# Display.net
KiCad netlist of a schematic drawn in Altium Designer
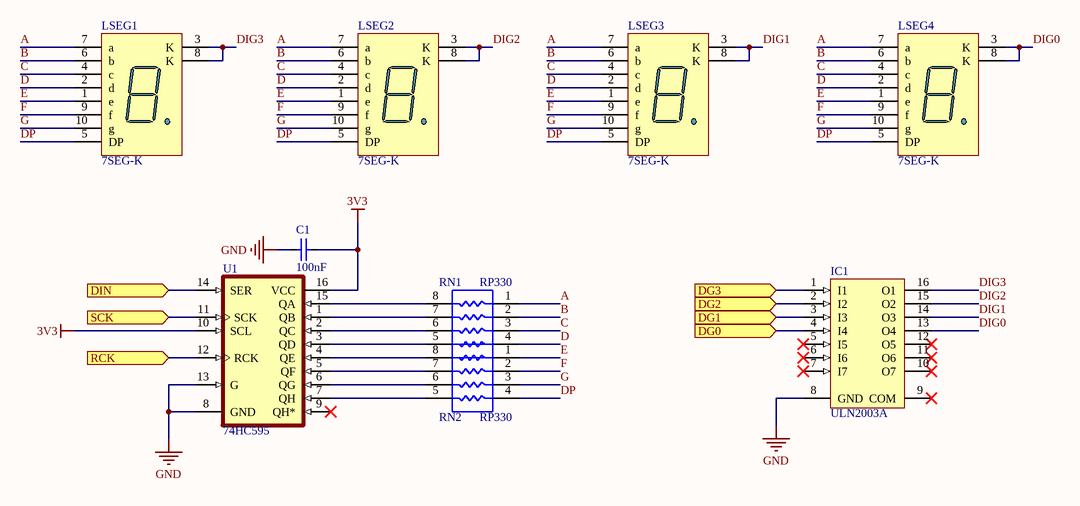
[diagram p0: Display.SchDoc]

(export (version "E")
  (design (tool "Eeschema 10.0.6"))
  (components
    (comp (ref "C1")
      (value "100nF")
      (footprint "CAP_0805")
      (description "Capacitor")
      (fields (field (name "PUBLISHER") "Altium Limited"))
      (libsource (lib "My Library") (part "CapSMD"))
    )
    (comp (ref "IC1")
      (value "ULN2003A")
      (footprint "SOIC16")
      (description "High-Voltage, High-Current Darlington Array")
      (fields (field (name "PUBLISHER") "Altium Limited"))
      (libsource (lib "My Library") (part "ULN2003A"))
    )
    (comp (ref "LSEG1")
      (value "7SEG-K")
      (footprint "LED7SEG")
      (description "14.2 mm General Purpose Blue 7-Segment Display: CC, RH DP, Gray Surface")
      (fields (field (name "PUBLISHER") "Altium Limited"))
      (libsource (lib "My Library") (part "LED7SEG-K"))
    )
    (comp (ref "LSEG2")
      (value "7SEG-K")
      (footprint "LED7SEG")
      (description "14.2 mm General Purpose Blue 7-Segment Display: CC, RH DP, Gray Surface")
      (fields (field (name "PUBLISHER") "Altium Limited"))
      (libsource (lib "My Library") (part "LED7SEG-K"))
    )
    (comp (ref "LSEG3")
      (value "7SEG-K")
      (footprint "LED7SEG")
      (description "14.2 mm General Purpose Blue 7-Segment Display: CC, RH DP, Gray Surface")
      (fields (field (name "PUBLISHER") "Altium Limited"))
      (libsource (lib "My Library") (part "LED7SEG-K"))
    )
    (comp (ref "LSEG4")
      (value "7SEG-K")
      (footprint "LED7SEG")
      (description "14.2 mm General Purpose Blue 7-Segment Display: CC, RH DP, Gray Surface")
      (fields (field (name "PUBLISHER") "Altium Limited"))
      (libsource (lib "My Library") (part "LED7SEG-K"))
    )
    (comp (ref "RN1") (value "RP330") (footprint "RN4-0805") (libsource (lib "My Library") (part "RN4-Dual")))
    (comp (ref "RN2") (value "RP330") (footprint "RN4-0805") (libsource (lib "My Library") (part "RN4-Dual")))
    (comp (ref "U1")
      (value "74HC595")
      (footprint "SOIC16")
      (description "8-bit Serial-Input/Serial or Parallel Output Shift Register with Latched 3-state Outputs")
      (libsource (lib "My Library") (part "74HC595"))
    )
  )
  (nets
    (net (code "1") (name "/A") (class "Default")
      (node (ref "LSEG1") (pin "7") (pinfunction "a_7") (pintype "passive"))
      (node (ref "LSEG2") (pin "7") (pinfunction "a_7") (pintype "passive"))
      (node (ref "LSEG3") (pin "7") (pinfunction "a_7") (pintype "passive"))
      (node (ref "LSEG4") (pin "7") (pinfunction "a_7") (pintype "passive"))
      (node (ref "RN1") (pin "1") (pinfunction "1_1") (pintype "passive"))
    )
    (net (code "2") (name "/B") (class "Default")
      (node (ref "LSEG1") (pin "6") (pinfunction "b_6") (pintype "passive"))
      (node (ref "LSEG2") (pin "6") (pinfunction "b_6") (pintype "passive"))
      (node (ref "LSEG3") (pin "6") (pinfunction "b_6") (pintype "passive"))
      (node (ref "LSEG4") (pin "6") (pinfunction "b_6") (pintype "passive"))
      (node (ref "RN1") (pin "2") (pinfunction "2_2") (pintype "passive"))
    )
    (net (code "3") (name "/C") (class "Default")
      (node (ref "LSEG1") (pin "4") (pinfunction "c_4") (pintype "passive"))
      (node (ref "LSEG2") (pin "4") (pinfunction "c_4") (pintype "passive"))
      (node (ref "LSEG3") (pin "4") (pinfunction "c_4") (pintype "passive"))
      (node (ref "LSEG4") (pin "4") (pinfunction "c_4") (pintype "passive"))
      (node (ref "RN1") (pin "3") (pinfunction "3_3") (pintype "passive"))
    )
    (net (code "4") (name "/D") (class "Default")
      (node (ref "LSEG1") (pin "2") (pinfunction "d_2") (pintype "passive"))
      (node (ref "LSEG2") (pin "2") (pinfunction "d_2") (pintype "passive"))
      (node (ref "LSEG3") (pin "2") (pinfunction "d_2") (pintype "passive"))
      (node (ref "LSEG4") (pin "2") (pinfunction "d_2") (pintype "passive"))
      (node (ref "RN1") (pin "4") (pinfunction "4_4") (pintype "passive"))
    )
    (net (code "5") (name "/DG0") (class "Default")
      (node (ref "IC1") (pin "4") (pinfunction "I4_4") (pintype "input"))
    )
    (net (code "6") (name "/DG1") (class "Default")
      (node (ref "IC1") (pin "3") (pinfunction "I3_3") (pintype "input"))
    )
    (net (code "7") (name "/DG2") (class "Default")
      (node (ref "IC1") (pin "2") (pinfunction "I2_2") (pintype "input"))
    )
    (net (code "8") (name "/DG3") (class "Default")
      (node (ref "IC1") (pin "1") (pinfunction "I1_1") (pintype "input"))
    )
    (net (code "9") (name "/DIG0") (class "Default")
      (node (ref "IC1") (pin "13") (pinfunction "O4_13") (pintype "open_collector"))
      (node (ref "LSEG4") (pin "3") (pinfunction "K_3") (pintype "passive"))
      (node (ref "LSEG4") (pin "8") (pinfunction "K_8") (pintype "passive"))
    )
    (net (code "10") (name "/DIG1") (class "Default")
      (node (ref "IC1") (pin "14") (pinfunction "O3_14") (pintype "open_collector"))
      (node (ref "LSEG3") (pin "3") (pinfunction "K_3") (pintype "passive"))
      (node (ref "LSEG3") (pin "8") (pinfunction "K_8") (pintype "passive"))
    )
    (net (code "11") (name "/DIG2") (class "Default")
      (node (ref "IC1") (pin "15") (pinfunction "O2_15") (pintype "open_collector"))
      (node (ref "LSEG2") (pin "3") (pinfunction "K_3") (pintype "passive"))
      (node (ref "LSEG2") (pin "8") (pinfunction "K_8") (pintype "passive"))
    )
    (net (code "12") (name "/DIG3") (class "Default")
      (node (ref "IC1") (pin "16") (pinfunction "O1_16") (pintype "open_collector"))
      (node (ref "LSEG1") (pin "3") (pinfunction "K_3") (pintype "passive"))
      (node (ref "LSEG1") (pin "8") (pinfunction "K_8") (pintype "passive"))
    )
    (net (code "13") (name "/DIN") (class "Default")
      (node (ref "U1") (pin "14") (pinfunction "SER_14") (pintype "input"))
    )
    (net (code "14") (name "/DP") (class "Default")
      (node (ref "LSEG1") (pin "5") (pinfunction "DP_5") (pintype "passive"))
      (node (ref "LSEG2") (pin "5") (pinfunction "DP_5") (pintype "passive"))
      (node (ref "LSEG3") (pin "5") (pinfunction "DP_5") (pintype "passive"))
      (node (ref "LSEG4") (pin "5") (pinfunction "DP_5") (pintype "passive"))
      (node (ref "RN2") (pin "4") (pinfunction "4_4") (pintype "passive"))
    )
    (net (code "15") (name "/E") (class "Default")
      (node (ref "LSEG1") (pin "1") (pinfunction "e_1") (pintype "passive"))
      (node (ref "LSEG2") (pin "1") (pinfunction "e_1") (pintype "passive"))
      (node (ref "LSEG3") (pin "1") (pinfunction "e_1") (pintype "passive"))
      (node (ref "LSEG4") (pin "1") (pinfunction "e_1") (pintype "passive"))
      (node (ref "RN2") (pin "1") (pinfunction "1_1") (pintype "passive"))
    )
    (net (code "16") (name "/F") (class "Default")
      (node (ref "LSEG1") (pin "9") (pinfunction "f_9") (pintype "passive"))
      (node (ref "LSEG2") (pin "9") (pinfunction "f_9") (pintype "passive"))
      (node (ref "LSEG3") (pin "9") (pinfunction "f_9") (pintype "passive"))
      (node (ref "LSEG4") (pin "9") (pinfunction "f_9") (pintype "passive"))
      (node (ref "RN2") (pin "2") (pinfunction "2_2") (pintype "passive"))
    )
    (net (code "17") (name "/G") (class "Default")
      (node (ref "LSEG1") (pin "10") (pinfunction "g_10") (pintype "passive"))
      (node (ref "LSEG2") (pin "10") (pinfunction "g_10") (pintype "passive"))
      (node (ref "LSEG3") (pin "10") (pinfunction "g_10") (pintype "passive"))
      (node (ref "LSEG4") (pin "10") (pinfunction "g_10") (pintype "passive"))
      (node (ref "RN2") (pin "3") (pinfunction "3_3") (pintype "passive"))
    )
    (net (code "18") (name "/RCK") (class "Default")
      (node (ref "U1") (pin "12") (pinfunction "RCK_12") (pintype "input"))
    )
    (net (code "19") (name "/SCK") (class "Default")
      (node (ref "U1") (pin "11") (pinfunction "SCK_11") (pintype "input"))
    )
    (net (code "20") (name "3V3") (class "Default")
      (node (ref "C1") (pin "1") (pinfunction "1_1") (pintype "passive"))
      (node (ref "U1") (pin "10") (pinfunction "SCL_10") (pintype "input"))
      (node (ref "U1") (pin "16") (pinfunction "VCC_16") (pintype "power_in"))
    )
    (net (code "21") (name "GND") (class "Default")
      (node (ref "C1") (pin "2") (pinfunction "2_2") (pintype "passive"))
      (node (ref "IC1") (pin "8") (pinfunction "GND_8") (pintype "power_in"))
      (node (ref "U1") (pin "13") (pinfunction "G_13") (pintype "input"))
      (node (ref "U1") (pin "8") (pinfunction "GND_8") (pintype "power_in"))
    )
    (net (code "22") (name "Net-(U1-QA)") (class "Default")
      (node (ref "RN1") (pin "8") (pinfunction "8_8") (pintype "passive"))
      (node (ref "U1") (pin "15") (pinfunction "QA_15") (pintype "input"))
    )
    (net (code "23") (name "Net-(U1-QB)") (class "Default")
      (node (ref "RN1") (pin "7") (pinfunction "7_7") (pintype "passive"))
      (node (ref "U1") (pin "1") (pinfunction "QB_1") (pintype "input"))
    )
    (net (code "24") (name "Net-(U1-QC)") (class "Default")
      (node (ref "RN1") (pin "6") (pinfunction "6_6") (pintype "passive"))
      (node (ref "U1") (pin "2") (pinfunction "QC_2") (pintype "input"))
    )
    (net (code "25") (name "Net-(U1-QD)") (class "Default")
      (node (ref "RN1") (pin "5") (pinfunction "5_5") (pintype "passive"))
      (node (ref "U1") (pin "3") (pinfunction "QD_3") (pintype "input"))
    )
    (net (code "26") (name "Net-(U1-QE)") (class "Default")
      (node (ref "RN2") (pin "8") (pinfunction "8_8") (pintype "passive"))
      (node (ref "U1") (pin "4") (pinfunction "QE_4") (pintype "input"))
    )
    (net (code "27") (name "Net-(U1-QF)") (class "Default")
      (node (ref "RN2") (pin "7") (pinfunction "7_7") (pintype "passive"))
      (node (ref "U1") (pin "5") (pinfunction "QF_5") (pintype "input"))
    )
    (net (code "28") (name "Net-(U1-QG)") (class "Default")
      (node (ref "RN2") (pin "6") (pinfunction "6_6") (pintype "passive"))
      (node (ref "U1") (pin "6") (pinfunction "QG_6") (pintype "input"))
    )
    (net (code "29") (name "Net-(U1-QH)") (class "Default")
      (node (ref "RN2") (pin "5") (pinfunction "5_5") (pintype "passive"))
      (node (ref "U1") (pin "7") (pinfunction "QH_7") (pintype "input"))
    )
    (net (code "30") (name "unconnected-(IC1-COM-Pad9)") (class "Default")
      (node (ref "IC1") (pin "9") (pinfunction "COM_9") (pintype "passive+no_connect"))
    )
    (net (code "31") (name "unconnected-(IC1-I5-Pad5)") (class "Default")
      (node (ref "IC1") (pin "5") (pinfunction "I5_5") (pintype "input+no_connect"))
    )
    (net (code "32") (name "unconnected-(IC1-I6-Pad6)") (class "Default")
      (node (ref "IC1") (pin "6") (pinfunction "I6_6") (pintype "input+no_connect"))
    )
    (net (code "33") (name "unconnected-(IC1-I7-Pad7)") (class "Default")
      (node (ref "IC1") (pin "7") (pinfunction "I7_7") (pintype "input+no_connect"))
    )
    (net (code "34") (name "unconnected-(IC1-O5-Pad12)") (class "Default")
      (node (ref "IC1") (pin "12") (pinfunction "O5_12") (pintype "open_collector+no_connect"))
    )
    (net (code "35") (name "unconnected-(IC1-O6-Pad11)") (class "Default")
      (node (ref "IC1") (pin "11") (pinfunction "O6_11") (pintype "open_collector+no_connect"))
    )
    (net (code "36") (name "unconnected-(IC1-O7-Pad10)") (class "Default")
      (node (ref "IC1") (pin "10") (pinfunction "O7_10") (pintype "open_collector+no_connect"))
    )
    (net (code "37") (name "unconnected-(U1-QH*-Pad9)") (class "Default")
      (node (ref "U1") (pin "9") (pinfunction "QH*_9") (pintype "input+no_connect"))
    )
  )
)
